# 3_mcu.net
KiCad netlist of a schematic drawn in Altium Designer
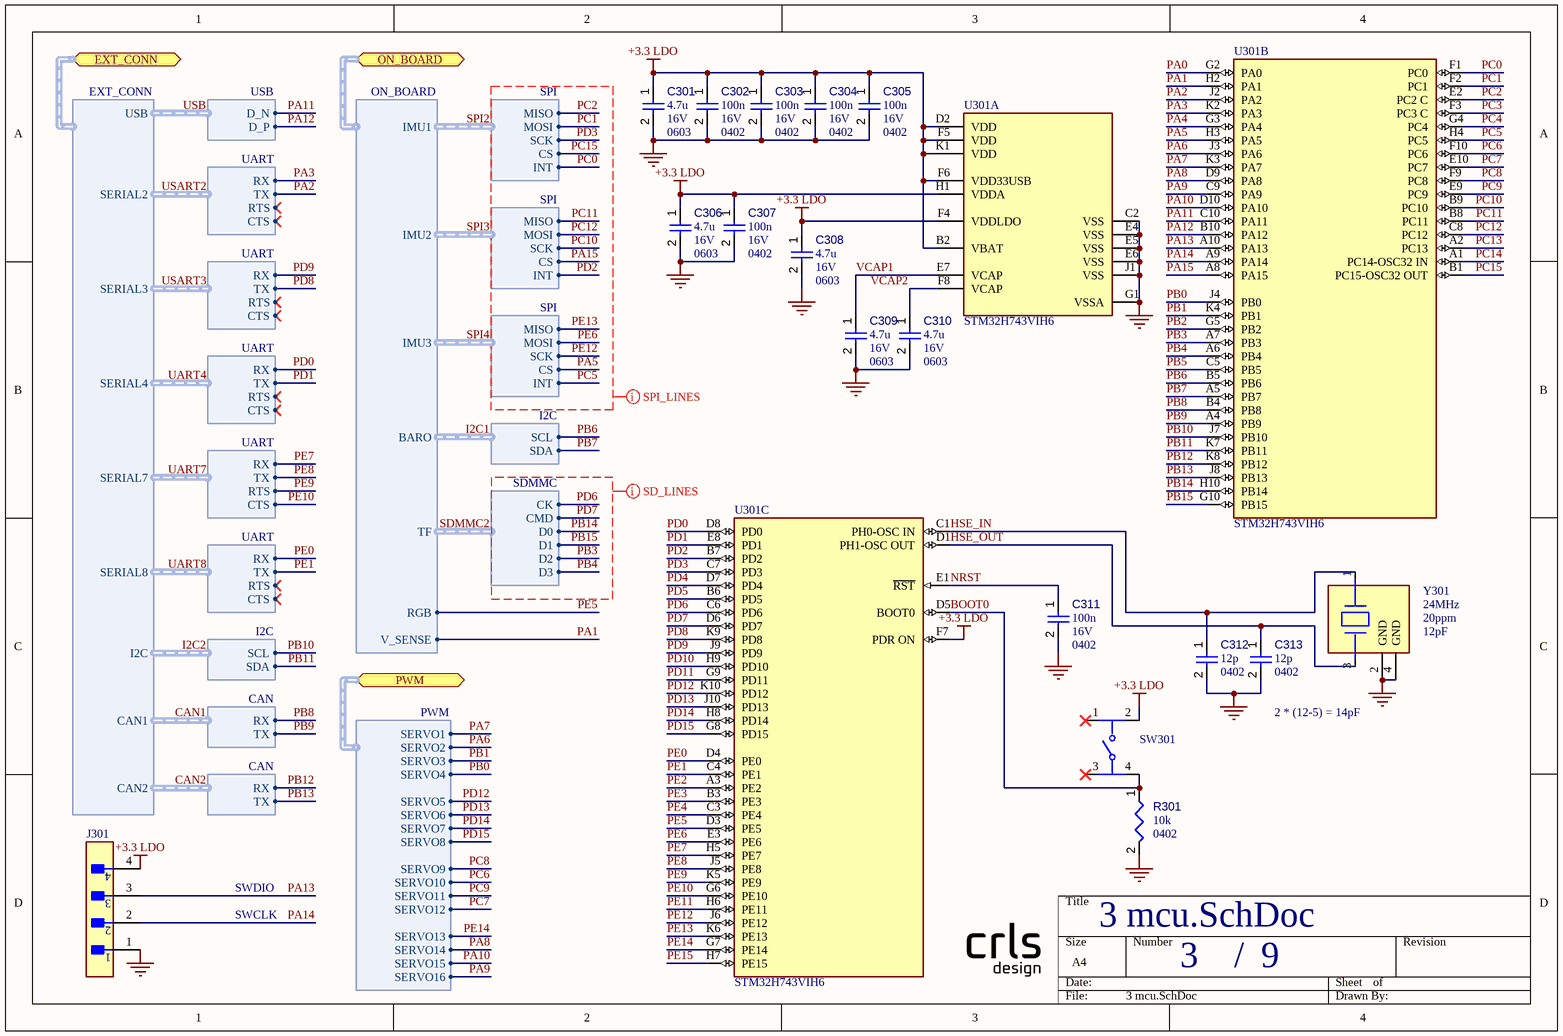
[diagram p0: 3 mcu.SchDoc]

(export (version "E")
  (design (tool "Eeschema 10.0.6"))
  (components
    (comp (ref "C301")
      (value "4.7u")
      (footprint "CAPC0603(1608)100_L")
      (description "Capacitor")
      (fields
        (field (name "CASE/PACKAGE") "0603")
        (field (name "VOLTAGE RATING") "16V")
        (field (name "Comment") "Capacitors,0603,4.7u,16V")
      )
      (libsource (lib "UBC Uncrewed Aircraft Systems") (part "CAP-NP-2"))
    )
    (comp (ref "C302")
      (value "100n")
      (footprint "CAPC0402(1005)60_L")
      (description "Capacitor")
      (fields
        (field (name "CASE/PACKAGE") "0402")
        (field (name "VOLTAGE RATING") "16V")
        (field (name "Comment") "Capacitors,0402,100n,16V")
      )
      (libsource (lib "UBC Uncrewed Aircraft Systems") (part "CAP-NP-2"))
    )
    (comp (ref "C303")
      (value "100n")
      (footprint "CAPC0402(1005)60_L")
      (description "Capacitor")
      (fields
        (field (name "CASE/PACKAGE") "0402")
        (field (name "VOLTAGE RATING") "16V")
        (field (name "Comment") "Capacitors,0402,100n,16V")
      )
      (libsource (lib "UBC Uncrewed Aircraft Systems") (part "CAP-NP-2"))
    )
    (comp (ref "C304")
      (value "100n")
      (footprint "CAPC0402(1005)60_L")
      (description "Capacitor")
      (fields
        (field (name "CASE/PACKAGE") "0402")
        (field (name "VOLTAGE RATING") "16V")
        (field (name "Comment") "Capacitors,0402,100n,16V")
      )
      (libsource (lib "UBC Uncrewed Aircraft Systems") (part "CAP-NP-2"))
    )
    (comp (ref "C305")
      (value "100n")
      (footprint "CAPC0402(1005)60_L")
      (description "Capacitor")
      (fields
        (field (name "CASE/PACKAGE") "0402")
        (field (name "VOLTAGE RATING") "16V")
        (field (name "Comment") "Capacitors,0402,100n,16V")
      )
      (libsource (lib "UBC Uncrewed Aircraft Systems") (part "CAP-NP-2"))
    )
    (comp (ref "C306")
      (value "4.7u")
      (footprint "CAPC0603(1608)100_L")
      (description "Capacitor")
      (fields
        (field (name "CASE/PACKAGE") "0603")
        (field (name "VOLTAGE RATING") "16V")
        (field (name "Comment") "Capacitors,0603,4.7u,16V")
      )
      (libsource (lib "UBC Uncrewed Aircraft Systems") (part "CAP-NP-2"))
    )
    (comp (ref "C307")
      (value "100n")
      (footprint "CAPC0402(1005)60_L")
      (description "Capacitor")
      (fields
        (field (name "CASE/PACKAGE") "0402")
        (field (name "VOLTAGE RATING") "16V")
        (field (name "Comment") "Capacitors,0402,100n,16V")
      )
      (libsource (lib "UBC Uncrewed Aircraft Systems") (part "CAP-NP-2"))
    )
    (comp (ref "C308")
      (value "4.7u")
      (footprint "CAPC0603(1608)100_L")
      (description "Capacitor")
      (fields
        (field (name "CASE/PACKAGE") "0603")
        (field (name "VOLTAGE RATING") "16V")
        (field (name "Comment") "Capacitors,0603,4.7u,16V")
      )
      (libsource (lib "UBC Uncrewed Aircraft Systems") (part "CAP-NP-2"))
    )
    (comp (ref "C309")
      (value "4.7u")
      (footprint "CAPC0603(1608)100_L")
      (description "Capacitor")
      (fields
        (field (name "CASE/PACKAGE") "0603")
        (field (name "VOLTAGE RATING") "16V")
        (field (name "Comment") "Capacitors,0603,4.7u,16V")
      )
      (libsource (lib "UBC Uncrewed Aircraft Systems") (part "CAP-NP-2"))
    )
    (comp (ref "C310")
      (value "4.7u")
      (footprint "CAPC0603(1608)100_L")
      (description "Capacitor")
      (fields
        (field (name "CASE/PACKAGE") "0603")
        (field (name "VOLTAGE RATING") "16V")
        (field (name "Comment") "Capacitors,0603,4.7u,16V")
      )
      (libsource (lib "UBC Uncrewed Aircraft Systems") (part "CAP-NP-2"))
    )
    (comp (ref "C311")
      (value "100n")
      (footprint "CAPC0402(1005)60_L")
      (description "Capacitor")
      (fields
        (field (name "CASE/PACKAGE") "0402")
        (field (name "VOLTAGE RATING") "16V")
        (field (name "Comment") "Capacitors,0402,100n,16V")
      )
      (libsource (lib "UBC Uncrewed Aircraft Systems") (part "CAP-NP-2"))
    )
    (comp (ref "C312")
      (value "12p")
      (footprint "CAPC0402(1005)60_L")
      (description "Capacitor")
      (fields (field (name "CASE/PACKAGE") "0402") (field (name "Comment") "Capacitors,0402,12p"))
      (libsource (lib "UBC Uncrewed Aircraft Systems") (part "CAP-NP-2"))
    )
    (comp (ref "C313")
      (value "12p")
      (footprint "CAPC0402(1005)60_L")
      (description "Capacitor")
      (fields (field (name "CASE/PACKAGE") "0402") (field (name "Comment") "Capacitors,0402,12p"))
      (libsource (lib "UBC Uncrewed Aircraft Systems") (part "CAP-NP-2"))
    )
    (comp (ref "J301")
      (value "MTLW-104-05-G-S-185")
      (footprint "FP-MTLW-104-05-G-S-185-MFG")
      (description "CONN HEADER VERT 4POS 2.54MM")
      (libsource (lib "Altium Content Vault") (part "299a8cea1bdcbc3624fe62c390fa72c"))
    )
    (comp (ref "R301")
      (value "10k")
      (footprint "RESC0402(1005)_L")
      (description "Resistor")
      (fields
        (field (name "CASE/PACKAGE") "0402")
        (field (name "TOLERANCE") "1%")
        (field (name "Comment") "Resistors,0402,1%,10k")
      )
      (libsource (lib "UBC Uncrewed Aircraft Systems") (part "RES-2"))
    )
    (comp (ref "SW301")
      (value "PTS810 SJG 250 SMTR LFS")
      (footprint "FP-PTS810_SJG_250_SMTR_LF-MFG")
      (description "SWITCH TACTILE SPST-NO 0.05A 16V")
      (fields
        (field (name "MANUFACTURER") "C&K Components")
        (field (name "OCTOPART") "https://octopart.com/pts810sjg250smtrlfs-c%26k+components-29380277")
      )
      (libsource (lib "Altium Content Vault") (part "1adf0dd01260c80cf25a44bfd6b99ba"))
    )
    (comp (ref "U301")
      (value "STM32H743VIH6")
      (footprint "FP-TFBGA100-A08Q-MFG")
      (description "HIGH-PERFORMANCE AND DSP WITH DP")
      (fields
        (field (name "OCTOPART") "https://octopart.com/stm32h743vih6-stmicroelectronics-93590710")
        (field (name "MANUFACTURER") "STMicroelectronics")
      )
      (libsource (lib "Altium Content Vault") (part "4bc6869135a8923a59641320c1dc386"))
    )
    (comp (ref "Y301")
      (value "TSX-3225 24.0000MF20G-AC3")
      (footprint "FP-TSX-3225-MFG")
      (description "CRYSTAL 24.0000MHZ 9PF SMD")
      (fields
        (field (name "FREQUENCY STABILITY") "20ppm")
        (field (name "LOAD CAPACITANCE") "12pF")
        (field (name "FREQUENCY") "24MHz")
        (field (name "TOLERANCE") "10ppm")
      )
      (libsource (lib "Altium Content Vault") (part "862d5228ea4a4c8f16e8fb874e464c7"))
    )
  )
  (nets
    (net (code "18") (name "+3.3 LDO") (class "Default")
      (node (ref "C301") (pin "1") (pinfunction "1_1") (pintype "passive"))
      (node (ref "C302") (pin "1") (pinfunction "1_1") (pintype "passive"))
      (node (ref "C303") (pin "1") (pinfunction "1_1") (pintype "passive"))
      (node (ref "C304") (pin "1") (pinfunction "1_1") (pintype "passive"))
      (node (ref "C305") (pin "1") (pinfunction "1_1") (pintype "passive"))
      (node (ref "C306") (pin "1") (pinfunction "1_1") (pintype "passive"))
      (node (ref "C307") (pin "1") (pinfunction "1_1") (pintype "passive"))
      (node (ref "C308") (pin "1") (pinfunction "1_1") (pintype "passive"))
      (node (ref "J301") (pin "4") (pinfunction "4_4") (pintype "passive"))
      (node (ref "SW301") (pin "2") (pinfunction "2_2") (pintype "passive"))
      (node (ref "U301") (pin "B2") (pinfunction "VBAT_B2") (pintype "power_in"))
      (node (ref "U301") (pin "D2") (pinfunction "VDD_D2") (pintype "power_in"))
      (node (ref "U301") (pin "F4") (pinfunction "VDDLDO_F4") (pintype "power_in"))
      (node (ref "U301") (pin "F5") (pinfunction "VDD_F5") (pintype "power_in"))
      (node (ref "U301") (pin "F6") (pinfunction "VDD33USB_F6") (pintype "power_in"))
      (node (ref "U301") (pin "F7") (pinfunction "PDR_ON_F7") (pintype "bidirectional"))
      (node (ref "U301") (pin "H1") (pinfunction "VDDA_H1") (pintype "power_in"))
      (node (ref "U301") (pin "K1") (pinfunction "VDD_K1") (pintype "power_in"))
    )
    (net (code "19") (name "/BOOT0") (class "Default")
      (node (ref "R301") (pin "1") (pinfunction "1_1") (pintype "passive"))
      (node (ref "SW301") (pin "4") (pinfunction "4_4") (pintype "passive"))
      (node (ref "U301") (pin "D5") (pinfunction "BOOT0_D5") (pintype "bidirectional"))
    )
    (net (code "23") (name "/HSE_IN") (class "Default")
      (node (ref "C312") (pin "1") (pinfunction "1_1") (pintype "passive"))
      (node (ref "U301") (pin "C1") (pinfunction "PH0-OSC_IN_C1") (pintype "bidirectional"))
      (node (ref "Y301") (pin "1") (pinfunction "1_1") (pintype "passive"))
    )
    (net (code "24") (name "/HSE_OUT") (class "Default")
      (node (ref "C313") (pin "1") (pinfunction "1_1") (pintype "passive"))
      (node (ref "U301") (pin "D1") (pinfunction "PH1-OSC_OUT_D1") (pintype "bidirectional"))
      (node (ref "Y301") (pin "3") (pinfunction "3_3") (pintype "passive"))
    )
    (net (code "27") (name "/NRST") (class "Default")
      (node (ref "C311") (pin "1") (pinfunction "1_1") (pintype "passive"))
      (node (ref "U301") (pin "E1") (pinfunction "~{RST}_E1") (pintype "input"))
    )
    (net (code "29") (name "/PA0") (class "Default")
      (node (ref "U301") (pin "G2") (pinfunction "PA0_G2") (pintype "bidirectional"))
    )
    (net (code "30") (name "/PA1") (class "Default")
      (node (ref "U301") (pin "H2") (pinfunction "PA1_H2") (pintype "bidirectional"))
    )
    (net (code "31") (name "/PA2") (class "Default")
      (node (ref "U301") (pin "J2") (pinfunction "PA2_J2") (pintype "bidirectional"))
    )
    (net (code "32") (name "/PA3") (class "Default")
      (node (ref "U301") (pin "K2") (pinfunction "PA3_K2") (pintype "bidirectional"))
    )
    (net (code "33") (name "/PA4") (class "Default")
      (node (ref "U301") (pin "G3") (pinfunction "PA4_G3") (pintype "bidirectional"))
    )
    (net (code "34") (name "/PA5") (class "Default")
      (node (ref "U301") (pin "H3") (pinfunction "PA5_H3") (pintype "bidirectional"))
    )
    (net (code "35") (name "/PA6") (class "Default")
      (node (ref "U301") (pin "J3") (pinfunction "PA6_J3") (pintype "bidirectional"))
    )
    (net (code "36") (name "/PA7") (class "Default")
      (node (ref "U301") (pin "K3") (pinfunction "PA7_K3") (pintype "bidirectional"))
    )
    (net (code "37") (name "/PA8") (class "Default")
      (node (ref "U301") (pin "D9") (pinfunction "PA8_D9") (pintype "bidirectional"))
    )
    (net (code "38") (name "/PA9") (class "Default")
      (node (ref "U301") (pin "C9") (pinfunction "PA9_C9") (pintype "bidirectional"))
    )
    (net (code "39") (name "/PA10") (class "Default")
      (node (ref "U301") (pin "D10") (pinfunction "PA10_D10") (pintype "bidirectional"))
    )
    (net (code "40") (name "/PA11") (class "Default")
      (node (ref "U301") (pin "C10") (pinfunction "PA11_C10") (pintype "bidirectional"))
    )
    (net (code "41") (name "/PA12") (class "Default")
      (node (ref "U301") (pin "B10") (pinfunction "PA12_B10") (pintype "bidirectional"))
    )
    (net (code "42") (name "/PA13") (class "Default")
      (node (ref "J301") (pin "3") (pinfunction "3_3") (pintype "passive"))
      (node (ref "U301") (pin "A10") (pinfunction "PA13_A10") (pintype "bidirectional"))
    )
    (net (code "43") (name "/PA14") (class "Default")
      (node (ref "J301") (pin "2") (pinfunction "2_2") (pintype "passive"))
      (node (ref "U301") (pin "A9") (pinfunction "PA14_A9") (pintype "bidirectional"))
    )
    (net (code "44") (name "/PA15") (class "Default")
      (node (ref "U301") (pin "A8") (pinfunction "PA15_A8") (pintype "bidirectional"))
    )
    (net (code "45") (name "/PB0") (class "Default")
      (node (ref "U301") (pin "J4") (pinfunction "PB0_J4") (pintype "bidirectional"))
    )
    (net (code "46") (name "/PB1") (class "Default")
      (node (ref "U301") (pin "K4") (pinfunction "PB1_K4") (pintype "bidirectional"))
    )
    (net (code "47") (name "/PB2") (class "Default")
      (node (ref "U301") (pin "G5") (pinfunction "PB2_G5") (pintype "bidirectional"))
    )
    (net (code "48") (name "/PB3") (class "Default")
      (node (ref "U301") (pin "A7") (pinfunction "PB3_A7") (pintype "bidirectional"))
    )
    (net (code "49") (name "/PB4") (class "Default")
      (node (ref "U301") (pin "A6") (pinfunction "PB4_A6") (pintype "bidirectional"))
    )
    (net (code "50") (name "/PB5") (class "Default")
      (node (ref "U301") (pin "C5") (pinfunction "PB5_C5") (pintype "bidirectional"))
    )
    (net (code "51") (name "/PB6") (class "Default")
      (node (ref "U301") (pin "B5") (pinfunction "PB6_B5") (pintype "bidirectional"))
    )
    (net (code "52") (name "/PB7") (class "Default")
      (node (ref "U301") (pin "A5") (pinfunction "PB7_A5") (pintype "bidirectional"))
    )
    (net (code "53") (name "/PB8") (class "Default")
      (node (ref "U301") (pin "B4") (pinfunction "PB8_B4") (pintype "bidirectional"))
    )
    (net (code "54") (name "/PB9") (class "Default")
      (node (ref "U301") (pin "A4") (pinfunction "PB9_A4") (pintype "bidirectional"))
    )
    (net (code "55") (name "/PB10") (class "Default")
      (node (ref "U301") (pin "J7") (pinfunction "PB10_J7") (pintype "bidirectional"))
    )
    (net (code "56") (name "/PB11") (class "Default")
      (node (ref "U301") (pin "K7") (pinfunction "PB11_K7") (pintype "bidirectional"))
    )
    (net (code "57") (name "/PB12") (class "Default")
      (node (ref "U301") (pin "K8") (pinfunction "PB12_K8") (pintype "bidirectional"))
    )
    (net (code "58") (name "/PB13") (class "Default")
      (node (ref "U301") (pin "J8") (pinfunction "PB13_J8") (pintype "bidirectional"))
    )
    (net (code "59") (name "/PB14") (class "Default")
      (node (ref "U301") (pin "H10") (pinfunction "PB14_H10") (pintype "bidirectional"))
    )
    (net (code "60") (name "/PB15") (class "Default")
      (node (ref "U301") (pin "G10") (pinfunction "PB15_G10") (pintype "bidirectional"))
    )
    (net (code "61") (name "/PC0") (class "Default")
      (node (ref "U301") (pin "F1") (pinfunction "PC0_F1") (pintype "bidirectional"))
    )
    (net (code "62") (name "/PC1") (class "Default")
      (node (ref "U301") (pin "F2") (pinfunction "PC1_F2") (pintype "bidirectional"))
    )
    (net (code "63") (name "/PC2") (class "Default")
      (node (ref "U301") (pin "E2") (pinfunction "PC2_C_E2") (pintype "bidirectional"))
    )
    (net (code "64") (name "/PC3") (class "Default")
      (node (ref "U301") (pin "F3") (pinfunction "PC3_C_F3") (pintype "bidirectional"))
    )
    (net (code "65") (name "/PC4") (class "Default")
      (node (ref "U301") (pin "G4") (pinfunction "PC4_G4") (pintype "bidirectional"))
    )
    (net (code "66") (name "/PC5") (class "Default")
      (node (ref "U301") (pin "H4") (pinfunction "PC5_H4") (pintype "bidirectional"))
    )
    (net (code "67") (name "/PC6") (class "Default")
      (node (ref "U301") (pin "F10") (pinfunction "PC6_F10") (pintype "bidirectional"))
    )
    (net (code "68") (name "/PC7") (class "Default")
      (node (ref "U301") (pin "E10") (pinfunction "PC7_E10") (pintype "bidirectional"))
    )
    (net (code "69") (name "/PC8") (class "Default")
      (node (ref "U301") (pin "F9") (pinfunction "PC8_F9") (pintype "bidirectional"))
    )
    (net (code "70") (name "/PC9") (class "Default")
      (node (ref "U301") (pin "E9") (pinfunction "PC9_E9") (pintype "bidirectional"))
    )
    (net (code "71") (name "/PC10") (class "Default")
      (node (ref "U301") (pin "B9") (pinfunction "PC10_B9") (pintype "bidirectional"))
    )
    (net (code "72") (name "/PC11") (class "Default")
      (node (ref "U301") (pin "B8") (pinfunction "PC11_B8") (pintype "bidirectional"))
    )
    (net (code "73") (name "/PC12") (class "Default")
      (node (ref "U301") (pin "C8") (pinfunction "PC12_C8") (pintype "bidirectional"))
    )
    (net (code "74") (name "/PC13") (class "Default")
      (node (ref "U301") (pin "A2") (pinfunction "PC13_A2") (pintype "bidirectional"))
    )
    (net (code "75") (name "/PC14") (class "Default")
      (node (ref "U301") (pin "A1") (pinfunction "PC14-OSC32_IN_A1") (pintype "bidirectional"))
    )
    (net (code "76") (name "/PC15") (class "Default")
      (node (ref "U301") (pin "B1") (pinfunction "PC15-OSC32_OUT_B1") (pintype "bidirectional"))
    )
    (net (code "77") (name "/PD0") (class "Default")
      (node (ref "U301") (pin "D8") (pinfunction "PD0_D8") (pintype "bidirectional"))
    )
    (net (code "78") (name "/PD1") (class "Default")
      (node (ref "U301") (pin "E8") (pinfunction "PD1_E8") (pintype "bidirectional"))
    )
    (net (code "79") (name "/PD2") (class "Default")
      (node (ref "U301") (pin "B7") (pinfunction "PD2_B7") (pintype "bidirectional"))
    )
    (net (code "80") (name "/PD3") (class "Default")
      (node (ref "U301") (pin "C7") (pinfunction "PD3_C7") (pintype "bidirectional"))
    )
    (net (code "81") (name "/PD4") (class "Default")
      (node (ref "U301") (pin "D7") (pinfunction "PD4_D7") (pintype "bidirectional"))
    )
    (net (code "82") (name "/PD5") (class "Default")
      (node (ref "U301") (pin "B6") (pinfunction "PD5_B6") (pintype "bidirectional"))
    )
    (net (code "83") (name "/PD6") (class "Default")
      (node (ref "U301") (pin "C6") (pinfunction "PD6_C6") (pintype "bidirectional"))
    )
    (net (code "84") (name "/PD7") (class "Default")
      (node (ref "U301") (pin "D6") (pinfunction "PD7_D6") (pintype "bidirectional"))
    )
    (net (code "85") (name "/PD8") (class "Default")
      (node (ref "U301") (pin "K9") (pinfunction "PD8_K9") (pintype "bidirectional"))
    )
    (net (code "86") (name "/PD9") (class "Default")
      (node (ref "U301") (pin "J9") (pinfunction "PD9_J9") (pintype "bidirectional"))
    )
    (net (code "87") (name "/PD10") (class "Default")
      (node (ref "U301") (pin "H9") (pinfunction "PD10_H9") (pintype "bidirectional"))
    )
    (net (code "88") (name "/PD11") (class "Default")
      (node (ref "U301") (pin "G9") (pinfunction "PD11_G9") (pintype "bidirectional"))
    )
    (net (code "89") (name "/PD12") (class "Default")
      (node (ref "U301") (pin "K10") (pinfunction "PD12_K10") (pintype "bidirectional"))
    )
    (net (code "90") (name "/PD13") (class "Default")
      (node (ref "U301") (pin "J10") (pinfunction "PD13_J10") (pintype "bidirectional"))
    )
    (net (code "91") (name "/PD14") (class "Default")
      (node (ref "U301") (pin "H8") (pinfunction "PD14_H8") (pintype "bidirectional"))
    )
    (net (code "92") (name "/PD15") (class "Default")
      (node (ref "U301") (pin "G8") (pinfunction "PD15_G8") (pintype "bidirectional"))
    )
    (net (code "93") (name "/PE0") (class "Default")
      (node (ref "U301") (pin "D4") (pinfunction "PE0_D4") (pintype "bidirectional"))
    )
    (net (code "94") (name "/PE1") (class "Default")
      (node (ref "U301") (pin "C4") (pinfunction "PE1_C4") (pintype "bidirectional"))
    )
    (net (code "95") (name "/PE2") (class "Default")
      (node (ref "U301") (pin "A3") (pinfunction "PE2_A3") (pintype "bidirectional"))
    )
    (net (code "96") (name "/PE3") (class "Default")
      (node (ref "U301") (pin "B3") (pinfunction "PE3_B3") (pintype "bidirectional"))
    )
    (net (code "97") (name "/PE4") (class "Default")
      (node (ref "U301") (pin "C3") (pinfunction "PE4_C3") (pintype "bidirectional"))
    )
    (net (code "98") (name "/PE5") (class "Default")
      (node (ref "U301") (pin "D3") (pinfunction "PE5_D3") (pintype "bidirectional"))
    )
    (net (code "99") (name "/PE6") (class "Default")
      (node (ref "U301") (pin "E3") (pinfunction "PE6_E3") (pintype "bidirectional"))
    )
    (net (code "100") (name "/PE7") (class "Default")
      (node (ref "U301") (pin "H5") (pinfunction "PE7_H5") (pintype "bidirectional"))
    )
    (net (code "101") (name "/PE8") (class "Default")
      (node (ref "U301") (pin "J5") (pinfunction "PE8_J5") (pintype "bidirectional"))
    )
    (net (code "102") (name "/PE9") (class "Default")
      (node (ref "U301") (pin "K5") (pinfunction "PE9_K5") (pintype "bidirectional"))
    )
    (net (code "103") (name "/PE10") (class "Default")
      (node (ref "U301") (pin "G6") (pinfunction "PE10_G6") (pintype "bidirectional"))
    )
    (net (code "104") (name "/PE11") (class "Default")
      (node (ref "U301") (pin "H6") (pinfunction "PE11_H6") (pintype "bidirectional"))
    )
    (net (code "105") (name "/PE12") (class "Default")
      (node (ref "U301") (pin "J6") (pinfunction "PE12_J6") (pintype "bidirectional"))
    )
    (net (code "106") (name "/PE13") (class "Default")
      (node (ref "U301") (pin "K6") (pinfunction "PE13_K6") (pintype "bidirectional"))
    )
    (net (code "107") (name "/PE14") (class "Default")
      (node (ref "U301") (pin "G7") (pinfunction "PE14_G7") (pintype "bidirectional"))
    )
    (net (code "108") (name "/PE15") (class "Default")
      (node (ref "U301") (pin "H7") (pinfunction "PE15_H7") (pintype "bidirectional"))
    )
    (net (code "119") (name "/VCAP1") (class "Default")
      (node (ref "C309") (pin "1") (pinfunction "1_1") (pintype "passive"))
      (node (ref "U301") (pin "E7") (pinfunction "VCAP_E7") (pintype "power_in"))
    )
    (net (code "120") (name "/VCAP2") (class "Default")
      (node (ref "C310") (pin "1") (pinfunction "1_1") (pintype "passive"))
      (node (ref "U301") (pin "F8") (pinfunction "VCAP_F8") (pintype "power_in"))
    )
    (net (code "122") (name "GND") (class "Default")
      (node (ref "C301") (pin "2") (pinfunction "2_2") (pintype "passive"))
      (node (ref "C302") (pin "2") (pinfunction "2_2") (pintype "passive"))
      (node (ref "C303") (pin "2") (pinfunction "2_2") (pintype "passive"))
      (node (ref "C304") (pin "2") (pinfunction "2_2") (pintype "passive"))
      (node (ref "C305") (pin "2") (pinfunction "2_2") (pintype "passive"))
      (node (ref "C306") (pin "2") (pinfunction "2_2") (pintype "passive"))
      (node (ref "C307") (pin "2") (pinfunction "2_2") (pintype "passive"))
      (node (ref "C308") (pin "2") (pinfunction "2_2") (pintype "passive"))
      (node (ref "C309") (pin "2") (pinfunction "2_2") (pintype "passive"))
      (node (ref "C310") (pin "2") (pinfunction "2_2") (pintype "passive"))
      (node (ref "C311") (pin "2") (pinfunction "2_2") (pintype "passive"))
      (node (ref "C312") (pin "2") (pinfunction "2_2") (pintype "passive"))
      (node (ref "C313") (pin "2") (pinfunction "2_2") (pintype "passive"))
      (node (ref "J301") (pin "1") (pinfunction "1_1") (pintype "passive"))
      (node (ref "R301") (pin "2") (pinfunction "2_2") (pintype "passive"))
      (node (ref "U301") (pin "C2") (pinfunction "VSS_C2") (pintype "power_in"))
      (node (ref "U301") (pin "E4") (pinfunction "VSS_E4") (pintype "power_in"))
      (node (ref "U301") (pin "E5") (pinfunction "VSS_E5") (pintype "power_in"))
      (node (ref "U301") (pin "E6") (pinfunction "VSS_E6") (pintype "power_in"))
      (node (ref "U301") (pin "G1") (pinfunction "VSSA_G1") (pintype "power_in"))
      (node (ref "U301") (pin "J1") (pinfunction "VSS_J1") (pintype "power_in"))
      (node (ref "Y301") (pin "2") (pinfunction "GND_2") (pintype "power_in"))
      (node (ref "Y301") (pin "4") (pinfunction "GND_4") (pintype "power_in"))
    )
    (net (code "123") (name "unconnected-(SW301-Pad1)") (class "Default")
      (node (ref "SW301") (pin "1") (pinfunction "1_1") (pintype "passive+no_connect"))
    )
    (net (code "124") (name "unconnected-(SW301-Pad3)") (class "Default")
      (node (ref "SW301") (pin "3") (pinfunction "3_3") (pintype "passive+no_connect"))
    )
  )
)
